# 03_SIMCOM.net
KiCad netlist of a schematic drawn in Altium Designer
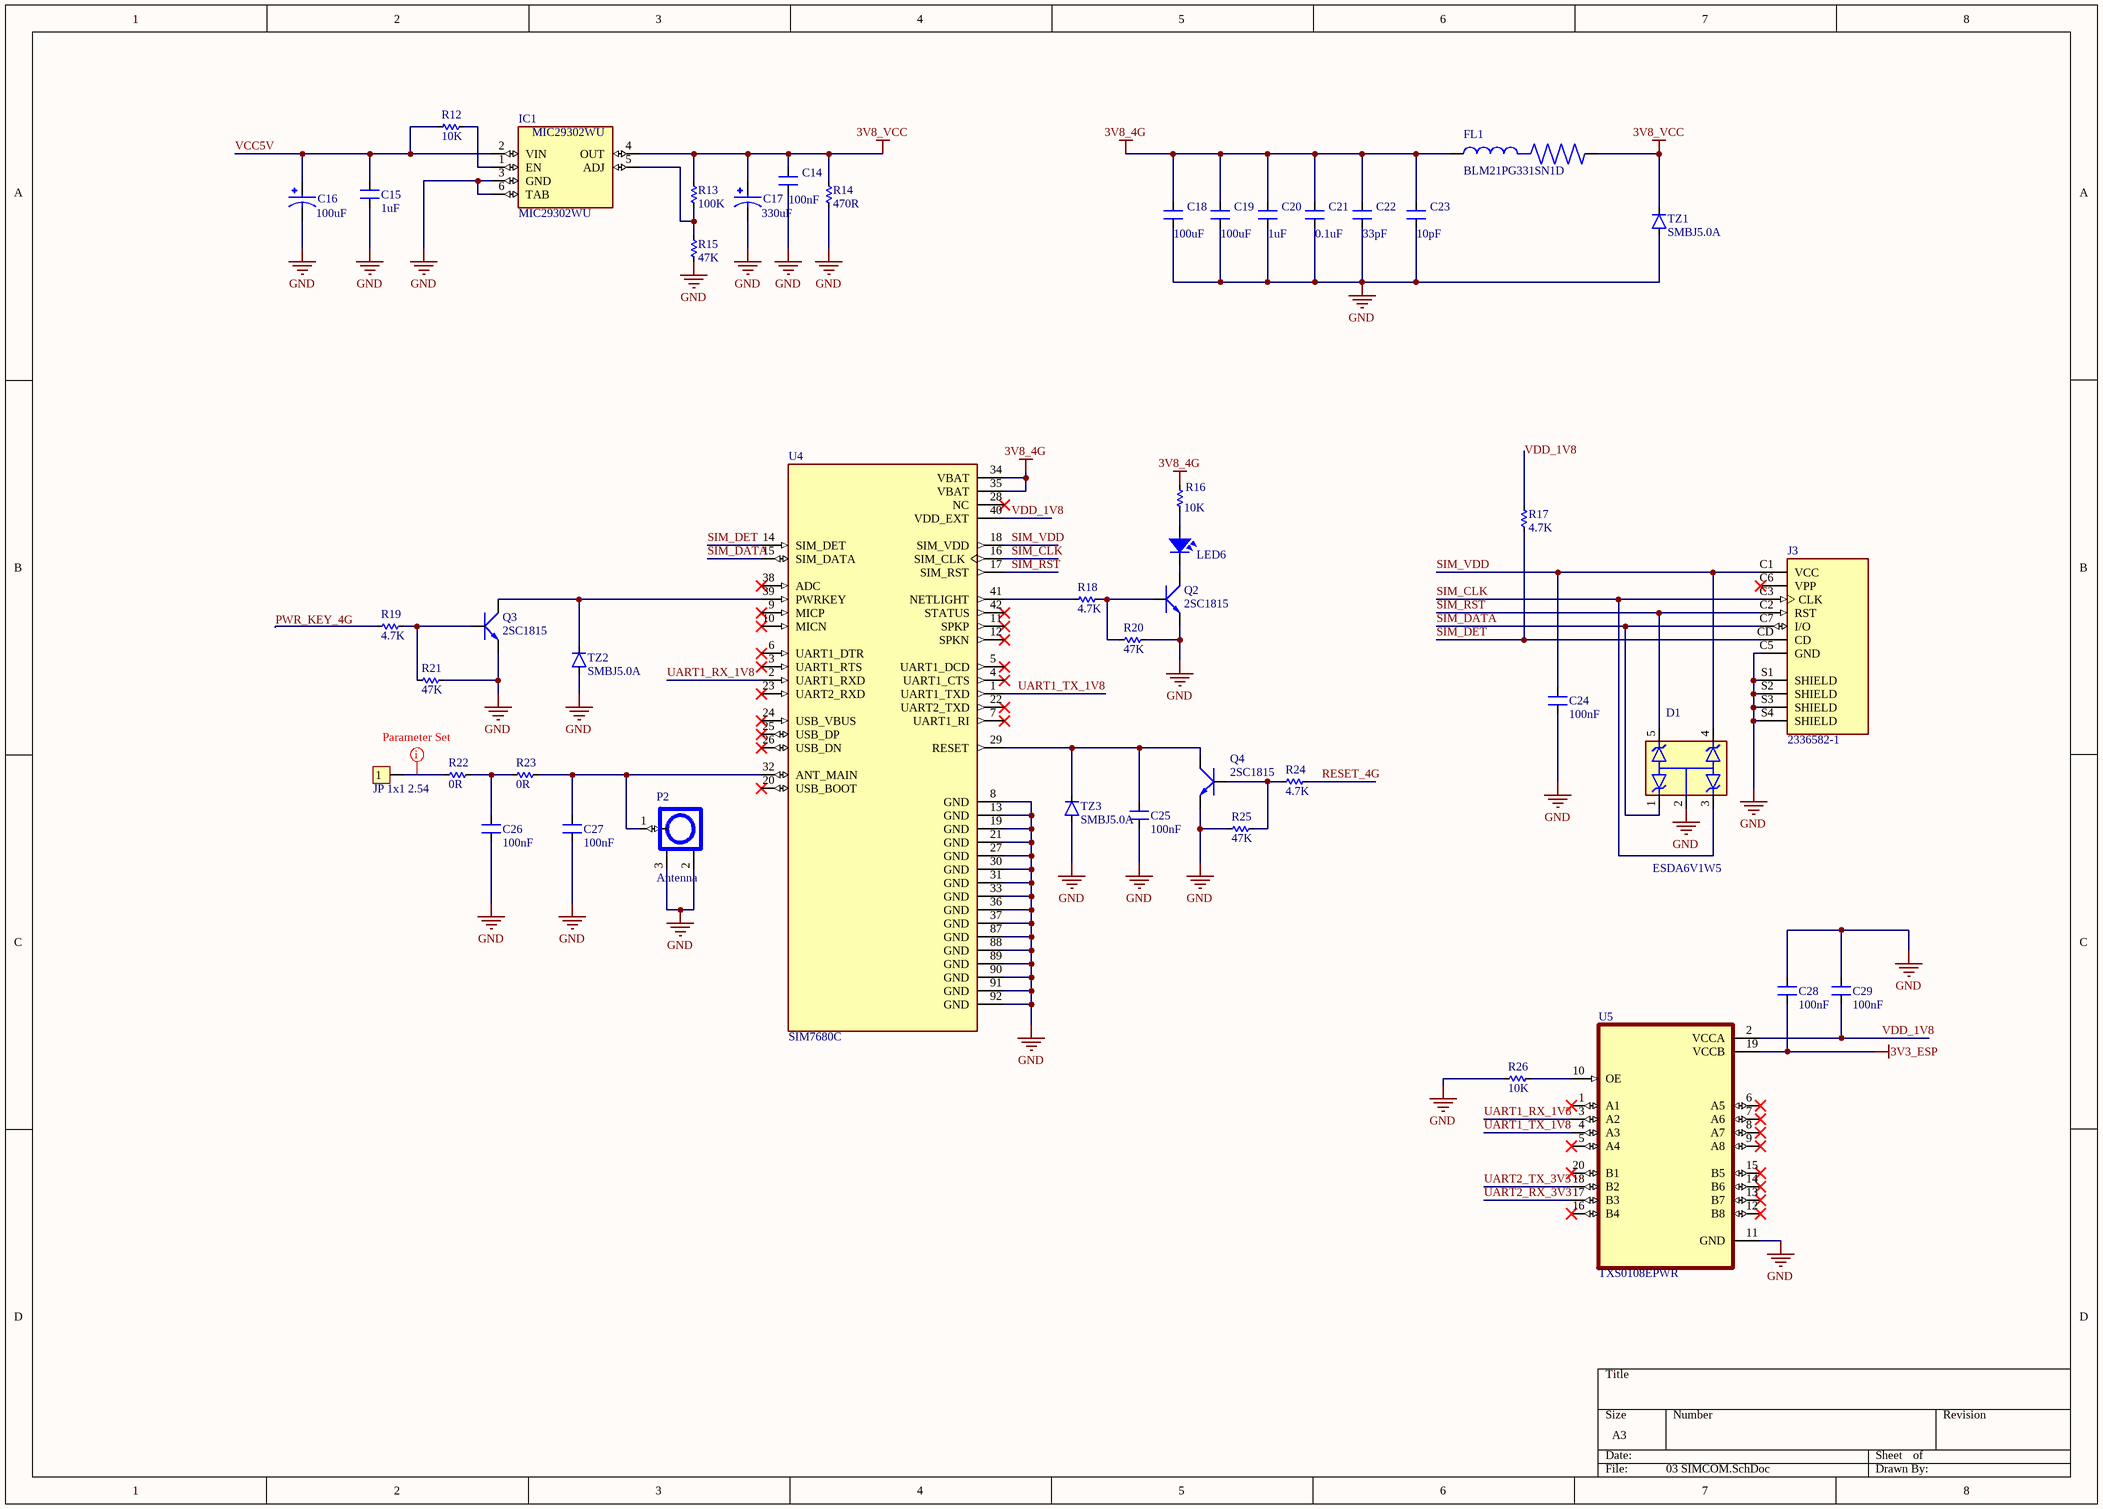
[diagram p0: 03 SIMCOM.SchDoc]

(export (version "E")
  (design (tool "Eeschema 10.0.6"))
  (components
    (comp (ref "C14")
      (value "100nF")
      (footprint "HuanHaui_FEETEAM:C 0603")
      (libsource (lib "THU_VIEN_TONG") (part "CAP_SMD"))
    )
    (comp (ref "C15")
      (value "1uF")
      (footprint "HuanHaui_FEETEAM:C 0603")
      (description "16V")
      (libsource (lib "HuanHaui_FEETEAM") (part "CAP_SMD"))
    )
    (comp (ref "C16")
      (value "100uF")
      (footprint "CAP_TANTALUM_3528")
      (description "Capacitor, Tantalum")
      (fields (field (name "MF") "AVX") (field (name "MP") "TAJB475K025RNJ"))
      (libsource (lib "My Library") (part "CAP_TANTALUM_SMD"))
    )
    (comp (ref "C17")
      (value "330uF")
      (footprint "CAP_TANTALUM_3528")
      (description "Capacitor, Tantalum")
      (fields (field (name "MF") "AVX") (field (name "MP") "TAJB475K025RNJ"))
      (libsource (lib "My Library") (part "CAP_TANTALUM_SMD"))
    )
    (comp (ref "C18")
      (value "100uF")
      (footprint "HuanHaui_FEETEAM:C 0603")
      (libsource (lib "THU_VIEN_TONG") (part "CAP_SMD"))
    )
    (comp (ref "C19")
      (value "100uF")
      (footprint "HuanHaui_FEETEAM:C 0603")
      (libsource (lib "THU_VIEN_TONG") (part "CAP_SMD"))
    )
    (comp (ref "C20")
      (value "1uF")
      (footprint "HuanHaui_FEETEAM:C 0603")
      (libsource (lib "THU_VIEN_TONG") (part "CAP_SMD"))
    )
    (comp (ref "C21")
      (value "0.1uF")
      (footprint "HuanHaui_FEETEAM:C 0603")
      (libsource (lib "THU_VIEN_TONG") (part "CAP_SMD"))
    )
    (comp (ref "C22")
      (value "33pF")
      (footprint "HuanHaui_FEETEAM:C 0603")
      (libsource (lib "THU_VIEN_TONG") (part "CAP_SMD"))
    )
    (comp (ref "C23")
      (value "10pF")
      (footprint "HuanHaui_FEETEAM:C 0603")
      (libsource (lib "THU_VIEN_TONG") (part "CAP_SMD"))
    )
    (comp (ref "C24")
      (value "100nF")
      (footprint "HuanHaui_FEETEAM:C 0603")
      (libsource (lib "HuanHaui_FEETEAM") (part "CAP_SMD"))
    )
    (comp (ref "C25")
      (value "100nF")
      (footprint "HuanHaui_FEETEAM:C 0603")
      (libsource (lib "HuanHaui_FEETEAM") (part "CAP_SMD"))
    )
    (comp (ref "C26")
      (value "100nF")
      (footprint "HuanHaui_FEETEAM:C 0603")
      (libsource (lib "HuanHaui_FEETEAM") (part "CAP_SMD"))
    )
    (comp (ref "C27")
      (value "100nF")
      (footprint "HuanHaui_FEETEAM:C 0603")
      (libsource (lib "HuanHaui_FEETEAM") (part "CAP_SMD"))
    )
    (comp (ref "C28")
      (value "100nF")
      (footprint "HuanHaui_FEETEAM:C 0603")
      (libsource (lib "HuanHaui_FEETEAM") (part "CAP_SMD"))
    )
    (comp (ref "C29")
      (value "100nF")
      (footprint "HuanHaui_FEETEAM:C 0603")
      (libsource (lib "HuanHaui_FEETEAM") (part "CAP_SMD"))
    )
    (comp (ref "D1")
      (value "ESDA6V1W5")
      (footprint "SOT65P210X110-5N")
      (description "- Clamp - Ipp Tvs Diode Surface Mount SOT-323-5")
      (fields (field (name "MF") "STMicroelectronics"))
      (libsource (lib "MinhNguyenCao") (part "ESDA6V1W5"))
    )
    (comp (ref "FL1")
      (value "BLM21PG331SN1D")
      (footprint "BEADC2012X105N")
      (description "SMD Ferrite 0805 330 Ohm +-25% 6000mA")
      (libsource (lib "MinhNguyenCao") (part "BLM21PG331SN1D"))
    )
    (comp (ref "IC1")
      (value "MIC29302WU")
      (footprint "MIC29302WU")
      (fields (field (name "MF") "{'manufacturer': u'Microchip Technology'}"))
      (libsource (lib "MinhNguyenCao") (part "MIC29302WU"))
    )
    (comp (ref "J3")
      (value "2336582-1")
      (footprint "TE_2336582-1")
      (description "PUSH-PUSH NANO SIM CONNECTOR")
      (libsource (lib "MinhNguyenCao") (part "2336582-1"))
    )
    (comp (ref "JP1")
      (value "JP 1x1 2.54")
      (footprint "JP 1x1 DT")
      (description "Cắm")
      (libsource (lib "Jump") (part "JP 1x1 2.54 Duc Cong"))
    )
    (comp (ref "LED6")
      (value "LED")
      (footprint "My Library:LED-0603")
      (libsource (lib "My Library") (part "LED SMD"))
    )
    (comp (ref "P2")
      (value "Antenna")
      (footprint "IPXS")
      (description "Antenna GSM GPS")
      (libsource (lib "My Library") (part "IPXSx66"))
    )
    (comp (ref "Q2")
      (value "2SC1815")
      (footprint "SOT23-321")
      (description "NPN 600mW, ECB")
      (libsource (lib "My Library") (part "2SC1815"))
    )
    (comp (ref "Q3")
      (value "2SC1815")
      (footprint "SOT23-321")
      (description "NPN 600mW, ECB")
      (libsource (lib "My Library") (part "2SC1815"))
    )
    (comp (ref "Q4")
      (value "2SC1815")
      (footprint "SOT23-321")
      (description "NPN 600mW, ECB")
      (libsource (lib "My Library") (part "2SC1815"))
    )
    (comp (ref "R12")
      (value "10K")
      (footprint "HuanHaui_FEETEAM:RES-SMD-0603")
      (description "RES_SMD")
      (fields
        (field (name "MANUFACTURER") "Generic Components")
        (field (name "PUBLISHER") "Altium Hobart Technology Centre")
      )
      (libsource (lib "HuanHaui_FEETEAM") (part "Res-SMD"))
    )
    (comp (ref "R13")
      (value "100K")
      (footprint "HuanHaui_FEETEAM:RES-SMD-0603")
      (description "RES_SMD")
      (fields
        (field (name "MANUFACTURER") "Generic Components")
        (field (name "PUBLISHER") "Altium Hobart Technology Centre")
      )
      (libsource (lib "HuanHaui_FEETEAM") (part "Res-SMD"))
    )
    (comp (ref "R14")
      (value "470R")
      (footprint "HuanHaui_FEETEAM:RES-SMD-0603")
      (description "RES_SMD")
      (fields
        (field (name "MANUFACTURER") "Generic Components")
        (field (name "PUBLISHER") "Altium Hobart Technology Centre")
      )
      (libsource (lib "HuanHaui_FEETEAM") (part "Res-SMD"))
    )
    (comp (ref "R15")
      (value "47K")
      (footprint "HuanHaui_FEETEAM:RES-SMD-0603")
      (description "RES_SMD")
      (fields
        (field (name "MANUFACTURER") "Generic Components")
        (field (name "PUBLISHER") "Altium Hobart Technology Centre")
      )
      (libsource (lib "HuanHaui_FEETEAM") (part "Res-SMD"))
    )
    (comp (ref "R16")
      (value "10K")
      (footprint "HuanHaui_FEETEAM:RES-SMD-0603")
      (description "RES_SMD")
      (fields
        (field (name "MANUFACTURER") "Generic Components")
        (field (name "PUBLISHER") "Altium Hobart Technology Centre")
      )
      (libsource (lib "HuanHaui_FEETEAM") (part "Res-SMD"))
    )
    (comp (ref "R17")
      (value "4.7K")
      (footprint "HuanHaui_FEETEAM:RES-SMD-0603")
      (description "RES_SMD")
      (fields
        (field (name "MANUFACTURER") "Generic Components")
        (field (name "PUBLISHER") "Altium Hobart Technology Centre")
      )
      (libsource (lib "HuanHaui_FEETEAM") (part "Res-SMD"))
    )
    (comp (ref "R18")
      (value "4.7K")
      (footprint "HuanHaui_FEETEAM:RES-SMD-0603")
      (description "RES_SMD")
      (fields
        (field (name "MANUFACTURER") "Generic Components")
        (field (name "PUBLISHER") "Altium Hobart Technology Centre")
      )
      (libsource (lib "HuanHaui_FEETEAM") (part "Res-SMD"))
    )
    (comp (ref "R19")
      (value "4.7K")
      (footprint "HuanHaui_FEETEAM:RES-SMD-0603")
      (description "RES_SMD")
      (fields
        (field (name "MANUFACTURER") "Generic Components")
        (field (name "PUBLISHER") "Altium Hobart Technology Centre")
      )
      (libsource (lib "HuanHaui_FEETEAM") (part "Res-SMD"))
    )
    (comp (ref "R20")
      (value "47K")
      (footprint "HuanHaui_FEETEAM:RES-SMD-0603")
      (description "RES_SMD")
      (fields
        (field (name "MANUFACTURER") "Generic Components")
        (field (name "PUBLISHER") "Altium Hobart Technology Centre")
      )
      (libsource (lib "HuanHaui_FEETEAM") (part "Res-SMD"))
    )
    (comp (ref "R21")
      (value "47K")
      (footprint "HuanHaui_FEETEAM:RES-SMD-0603")
      (description "RES_SMD")
      (fields
        (field (name "MANUFACTURER") "Generic Components")
        (field (name "PUBLISHER") "Altium Hobart Technology Centre")
      )
      (libsource (lib "HuanHaui_FEETEAM") (part "Res-SMD"))
    )
    (comp (ref "R22")
      (value "0R")
      (footprint "HuanHaui_FEETEAM:RES-SMD-0603")
      (description "RES_SMD")
      (fields
        (field (name "MANUFACTURER") "Generic Components")
        (field (name "PUBLISHER") "Altium Hobart Technology Centre")
      )
      (libsource (lib "HuanHaui_FEETEAM") (part "Res-SMD"))
    )
    (comp (ref "R23")
      (value "0R")
      (footprint "HuanHaui_FEETEAM:RES-SMD-0603")
      (description "RES_SMD")
      (fields
        (field (name "MANUFACTURER") "Generic Components")
        (field (name "PUBLISHER") "Altium Hobart Technology Centre")
      )
      (libsource (lib "HuanHaui_FEETEAM") (part "Res-SMD"))
    )
    (comp (ref "R24")
      (value "4.7K")
      (footprint "HuanHaui_FEETEAM:RES-SMD-0603")
      (description "RES_SMD")
      (fields
        (field (name "MANUFACTURER") "Generic Components")
        (field (name "PUBLISHER") "Altium Hobart Technology Centre")
      )
      (libsource (lib "HuanHaui_FEETEAM") (part "Res-SMD"))
    )
    (comp (ref "R25")
      (value "47K")
      (footprint "HuanHaui_FEETEAM:RES-SMD-0603")
      (description "RES_SMD")
      (fields
        (field (name "MANUFACTURER") "Generic Components")
        (field (name "PUBLISHER") "Altium Hobart Technology Centre")
      )
      (libsource (lib "HuanHaui_FEETEAM") (part "Res-SMD"))
    )
    (comp (ref "R26")
      (value "10K")
      (footprint "HuanHaui_FEETEAM:RES-SMD-0603")
      (description "RES_SMD")
      (fields
        (field (name "MANUFACTURER") "Generic Components")
        (field (name "PUBLISHER") "Altium Hobart Technology Centre")
      )
      (libsource (lib "HuanHaui_FEETEAM") (part "Res-SMD"))
    )
    (comp (ref "TZ1")
      (value "SMBJ5.0A")
      (footprint "SMB")
      (description "9.2V Clamp 65.3A Ipp Tvs Diode Surface Mount DO-214AA _SMBJ_")
      (fields (field (name "MF") "Littelfuse"))
      (libsource (lib "MinhNguyenCao") (part "SMBJ5.0A"))
    )
    (comp (ref "TZ2")
      (value "SMBJ5.0A")
      (footprint "SMB")
      (description "9.2V Clamp 65.3A Ipp Tvs Diode Surface Mount DO-214AA _SMBJ_")
      (fields (field (name "MF") "Littelfuse"))
      (libsource (lib "MinhNguyenCao") (part "SMBJ5.0A"))
    )
    (comp (ref "TZ3")
      (value "SMBJ5.0A")
      (footprint "SMB")
      (description "9.2V Clamp 65.3A Ipp Tvs Diode Surface Mount DO-214AA _SMBJ_")
      (fields (field (name "MF") "Littelfuse"))
      (libsource (lib "MinhNguyenCao") (part "SMBJ5.0A"))
    )
    (comp (ref "U4")
      (value "SIM7680C")
      (footprint "LCC110P1570X1760X250-42N")
      (description "Module: GSM/Bluetooth; GPRS; 2G; 1800MHz, 900MHz; 85.6kbps; SMD")
      (fields (field (name "MP") "SIM800C") (field (name "MF") "Simcom"))
      (libsource (lib "MinhNguyenCao") (part "SIM7680C"))
    )
    (comp (ref "U5")
      (value "TXS0108EPWR")
      (footprint "SOP65P640X120-20N")
      (description "8-bit bidirectional voltage-level shifter for open-drain and push-pull application")
      (fields (field (name "MF") "Texas Instruments"))
      (libsource (lib "MinhNguyenCao") (part "TXS0108EPWR"))
    )
  )
  (nets
    (net (code "1") (name "/PWR_KEY_4G") (class "Default")
      (node (ref "R19") (pin "1") (pinfunction "1_1") (pintype "passive"))
    )
    (net (code "2") (name "/RESET_4G") (class "Default")
      (node (ref "R24") (pin "2") (pinfunction "2_2") (pintype "passive"))
    )
    (net (code "3") (name "/SIM_CLK") (class "Default")
      (node (ref "D1") (pin "3") (pinfunction "3_3") (pintype "passive"))
      (node (ref "J3") (pin "C3") (pinfunction "CLK_C3") (pintype "input"))
      (node (ref "U4") (pin "16") (pinfunction "SIM_CLK_16") (pintype "output"))
    )
    (net (code "4") (name "/SIM_DATA") (class "Default")
      (node (ref "D1") (pin "1") (pinfunction "1_1") (pintype "passive"))
      (node (ref "J3") (pin "C7") (pinfunction "I/O_C7") (pintype "bidirectional"))
      (node (ref "U4") (pin "15") (pinfunction "SIM_DATA_15") (pintype "bidirectional"))
    )
    (net (code "5") (name "/SIM_DET") (class "Default")
      (node (ref "J3") (pin "CD") (pinfunction "CD_CD") (pintype "passive"))
      (node (ref "R17") (pin "2") (pinfunction "2_2") (pintype "passive"))
      (node (ref "U4") (pin "14") (pinfunction "SIM_DET_14") (pintype "input"))
    )
    (net (code "6") (name "/SIM_RST") (class "Default")
      (node (ref "D1") (pin "5") (pinfunction "5_5") (pintype "passive"))
      (node (ref "J3") (pin "C2") (pinfunction "RST_C2") (pintype "input"))
      (node (ref "U4") (pin "17") (pinfunction "SIM_RST_17") (pintype "output"))
    )
    (net (code "7") (name "/SIM_VDD") (class "Default")
      (node (ref "C24") (pin "2") (pinfunction "2_2") (pintype "passive"))
      (node (ref "D1") (pin "4") (pinfunction "4_4") (pintype "passive"))
      (node (ref "J3") (pin "C1") (pinfunction "VCC_C1") (pintype "power_in"))
      (node (ref "U4") (pin "18") (pinfunction "SIM_VDD_18") (pintype "output"))
    )
    (net (code "8") (name "/UART1_RX_1V8") (class "Default")
      (node (ref "U4") (pin "2") (pinfunction "UART1_RXD_2") (pintype "input"))
      (node (ref "U5") (pin "3") (pinfunction "A2_3") (pintype "bidirectional"))
    )
    (net (code "9") (name "/UART1_TX_1V8") (class "Default")
      (node (ref "U4") (pin "1") (pinfunction "UART1_TXD_1") (pintype "output"))
      (node (ref "U5") (pin "4") (pinfunction "A3_4") (pintype "bidirectional"))
    )
    (net (code "10") (name "/UART2_RX_3V3") (class "Default")
      (node (ref "U5") (pin "17") (pinfunction "B3_17") (pintype "bidirectional"))
    )
    (net (code "11") (name "/UART2_TX_3V3") (class "Default")
      (node (ref "U5") (pin "18") (pinfunction "B2_18") (pintype "bidirectional"))
    )
    (net (code "12") (name "/VCC5V") (class "Default")
      (node (ref "C15") (pin "2") (pinfunction "2_2") (pintype "passive"))
      (node (ref "C16") (pin "1") (pinfunction "1_1") (pintype "passive"))
      (node (ref "IC1") (pin "2") (pinfunction "VIN_2") (pintype "bidirectional"))
      (node (ref "R12") (pin "1") (pinfunction "1_1") (pintype "passive"))
    )
    (net (code "13") (name "/VDD_1V8") (class "Default")
      (node (ref "C29") (pin "1") (pinfunction "1_1") (pintype "passive"))
      (node (ref "R17") (pin "1") (pinfunction "1_1") (pintype "passive"))
      (node (ref "U4") (pin "40") (pinfunction "VDD_EXT_40") (pintype "power_in"))
      (node (ref "U5") (pin "2") (pinfunction "VCCA_2") (pintype "power_in"))
    )
    (net (code "14") (name "3V3_ESP") (class "Default")
      (node (ref "C28") (pin "1") (pinfunction "1_1") (pintype "passive"))
      (node (ref "U5") (pin "19") (pinfunction "VCCB_19") (pintype "power_in"))
    )
    (net (code "15") (name "3V8_4G") (class "Default")
      (node (ref "C18") (pin "1") (pinfunction "1_1") (pintype "passive"))
      (node (ref "C19") (pin "1") (pinfunction "1_1") (pintype "passive"))
      (node (ref "C20") (pin "1") (pinfunction "1_1") (pintype "passive"))
      (node (ref "C21") (pin "1") (pinfunction "1_1") (pintype "passive"))
      (node (ref "C22") (pin "1") (pinfunction "1_1") (pintype "passive"))
      (node (ref "C23") (pin "1") (pinfunction "1_1") (pintype "passive"))
      (node (ref "FL1") (pin "1") (pinfunction "1_1") (pintype "passive"))
      (node (ref "R16") (pin "2") (pinfunction "2_2") (pintype "passive"))
      (node (ref "U4") (pin "34") (pinfunction "VBAT_34") (pintype "power_in"))
      (node (ref "U4") (pin "35") (pinfunction "VBAT_35") (pintype "power_in"))
    )
    (net (code "16") (name "3V8_VCC") (class "Default")
      (node (ref "C14") (pin "1") (pinfunction "1_1") (pintype "passive"))
      (node (ref "C17") (pin "1") (pinfunction "1_1") (pintype "passive"))
      (node (ref "FL1") (pin "2") (pinfunction "2_2") (pintype "passive"))
      (node (ref "IC1") (pin "4") (pinfunction "OUT_4") (pintype "bidirectional"))
      (node (ref "R13") (pin "1") (pinfunction "1_1") (pintype "passive"))
      (node (ref "R14") (pin "1") (pinfunction "1_1") (pintype "passive"))
      (node (ref "TZ1") (pin "2") (pinfunction "2_2") (pintype "passive"))
    )
    (net (code "17") (name "GND") (class "Default")
      (node (ref "C14") (pin "2") (pinfunction "2_2") (pintype "passive"))
      (node (ref "C15") (pin "1") (pinfunction "1_1") (pintype "passive"))
      (node (ref "C16") (pin "2") (pinfunction "2_2") (pintype "passive"))
      (node (ref "C17") (pin "2") (pinfunction "2_2") (pintype "passive"))
      (node (ref "C18") (pin "2") (pinfunction "2_2") (pintype "passive"))
      (node (ref "C19") (pin "2") (pinfunction "2_2") (pintype "passive"))
      (node (ref "C20") (pin "2") (pinfunction "2_2") (pintype "passive"))
      (node (ref "C21") (pin "2") (pinfunction "2_2") (pintype "passive"))
      (node (ref "C22") (pin "2") (pinfunction "2_2") (pintype "passive"))
      (node (ref "C23") (pin "2") (pinfunction "2_2") (pintype "passive"))
      (node (ref "C24") (pin "1") (pinfunction "1_1") (pintype "passive"))
      (node (ref "C25") (pin "1") (pinfunction "1_1") (pintype "passive"))
      (node (ref "C26") (pin "1") (pinfunction "1_1") (pintype "passive"))
      (node (ref "C27") (pin "1") (pinfunction "1_1") (pintype "passive"))
      (node (ref "C28") (pin "2") (pinfunction "2_2") (pintype "passive"))
      (node (ref "C29") (pin "2") (pinfunction "2_2") (pintype "passive"))
      (node (ref "D1") (pin "2") (pinfunction "2_2") (pintype "passive"))
      (node (ref "IC1") (pin "3") (pinfunction "GND_3") (pintype "bidirectional"))
      (node (ref "IC1") (pin "6") (pinfunction "TAB_6") (pintype "bidirectional"))
      (node (ref "J3") (pin "C5") (pinfunction "GND_C5") (pintype "power_in"))
      (node (ref "J3") (pin "S1") (pinfunction "SHIELD_S1") (pintype "passive"))
      (node (ref "J3") (pin "S2") (pinfunction "SHIELD_S2") (pintype "passive"))
      (node (ref "J3") (pin "S3") (pinfunction "SHIELD_S3") (pintype "passive"))
      (node (ref "J3") (pin "S4") (pinfunction "SHIELD_S4") (pintype "passive"))
      (node (ref "P2") (pin "2") (pintype "passive"))
      (node (ref "P2") (pin "3") (pintype "passive"))
      (node (ref "Q2") (pin "1") (pinfunction "E_1") (pintype "passive"))
      (node (ref "Q3") (pin "1") (pinfunction "E_1") (pintype "passive"))
      (node (ref "Q4") (pin "1") (pinfunction "E_1") (pintype "passive"))
      (node (ref "R14") (pin "2") (pinfunction "2_2") (pintype "passive"))
      (node (ref "R15") (pin "2") (pinfunction "2_2") (pintype "passive"))
      (node (ref "R20") (pin "2") (pinfunction "2_2") (pintype "passive"))
      (node (ref "R21") (pin "1") (pinfunction "1_1") (pintype "passive"))
      (node (ref "R25") (pin "2") (pinfunction "2_2") (pintype "passive"))
      (node (ref "R26") (pin "2") (pinfunction "2_2") (pintype "passive"))
      (node (ref "TZ1") (pin "1") (pinfunction "1_1") (pintype "passive"))
      (node (ref "TZ2") (pin "1") (pinfunction "1_1") (pintype "passive"))
      (node (ref "TZ3") (pin "1") (pinfunction "1_1") (pintype "passive"))
      (node (ref "U4") (pin "13") (pinfunction "GND_13") (pintype "power_in"))
      (node (ref "U4") (pin "19") (pinfunction "GND_19") (pintype "power_in"))
      (node (ref "U4") (pin "21") (pinfunction "GND_21") (pintype "power_in"))
      (node (ref "U4") (pin "27") (pinfunction "GND_27") (pintype "power_in"))
      (node (ref "U4") (pin "30") (pinfunction "GND_30") (pintype "power_in"))
      (node (ref "U4") (pin "31") (pinfunction "GND_31") (pintype "power_in"))
      (node (ref "U4") (pin "33") (pinfunction "GND_33") (pintype "power_in"))
      (node (ref "U4") (pin "36") (pinfunction "GND_36") (pintype "power_in"))
      (node (ref "U4") (pin "37") (pinfunction "GND_37") (pintype "power_in"))
      (node (ref "U4") (pin "8") (pinfunction "GND_8") (pintype "power_in"))
      (node (ref "U4") (pin "87") (pinfunction "GND_87") (pintype "power_in"))
      (node (ref "U4") (pin "88") (pinfunction "GND_88") (pintype "power_in"))
      (node (ref "U4") (pin "89") (pinfunction "GND_89") (pintype "power_in"))
      (node (ref "U4") (pin "90") (pinfunction "GND_90") (pintype "power_in"))
      (node (ref "U4") (pin "91") (pinfunction "GND_91") (pintype "power_in"))
      (node (ref "U4") (pin "92") (pinfunction "GND_92") (pintype "power_in"))
      (node (ref "U5") (pin "11") (pinfunction "GND_11") (pintype "power_in"))
    )
    (net (code "18") (name "Net-(C26-Pad2)") (class "Default")
      (node (ref "C26") (pin "2") (pinfunction "2_2") (pintype "passive"))
      (node (ref "R22") (pin "1") (pinfunction "1_1") (pintype "passive"))
      (node (ref "R23") (pin "2") (pinfunction "2_2") (pintype "passive"))
    )
    (net (code "19") (name "Net-(IC1-ADJ)") (class "Default")
      (node (ref "IC1") (pin "5") (pinfunction "ADJ_5") (pintype "bidirectional"))
      (node (ref "R13") (pin "2") (pinfunction "2_2") (pintype "passive"))
      (node (ref "R15") (pin "1") (pinfunction "1_1") (pintype "passive"))
    )
    (net (code "20") (name "Net-(IC1-EN)") (class "Default")
      (node (ref "IC1") (pin "1") (pinfunction "EN_1") (pintype "bidirectional"))
      (node (ref "R12") (pin "2") (pinfunction "2_2") (pintype "passive"))
    )
    (net (code "21") (name "Net-(JP1-Pad1)") (class "Default")
      (node (ref "JP1") (pin "1") (pinfunction "1_1") (pintype "passive"))
      (node (ref "R22") (pin "2") (pinfunction "2_2") (pintype "passive"))
    )
    (net (code "22") (name "Net-(LED6-Pad1)") (class "Default")
      (node (ref "LED6") (pin "1") (pinfunction "1_1") (pintype "passive"))
      (node (ref "R16") (pin "1") (pinfunction "1_1") (pintype "passive"))
    )
    (net (code "23") (name "Net-(Q2-B)") (class "Default")
      (node (ref "Q2") (pin "3") (pinfunction "B_3") (pintype "passive"))
      (node (ref "R18") (pin "2") (pinfunction "2_2") (pintype "passive"))
      (node (ref "R20") (pin "1") (pinfunction "1_1") (pintype "passive"))
    )
    (net (code "24") (name "Net-(Q2-C)") (class "Default")
      (node (ref "LED6") (pin "2") (pinfunction "2_2") (pintype "passive"))
      (node (ref "Q2") (pin "2") (pinfunction "C_2") (pintype "passive"))
    )
    (net (code "25") (name "Net-(Q3-B)") (class "Default")
      (node (ref "Q3") (pin "3") (pinfunction "B_3") (pintype "passive"))
      (node (ref "R19") (pin "2") (pinfunction "2_2") (pintype "passive"))
      (node (ref "R21") (pin "2") (pinfunction "2_2") (pintype "passive"))
    )
    (net (code "26") (name "Net-(Q3-C)") (class "Default")
      (node (ref "Q3") (pin "2") (pinfunction "C_2") (pintype "passive"))
      (node (ref "TZ2") (pin "2") (pinfunction "2_2") (pintype "passive"))
      (node (ref "U4") (pin "39") (pinfunction "PWRKEY_39") (pintype "input"))
    )
    (net (code "27") (name "Net-(Q4-B)") (class "Default")
      (node (ref "Q4") (pin "3") (pinfunction "B_3") (pintype "passive"))
      (node (ref "R24") (pin "1") (pinfunction "1_1") (pintype "passive"))
      (node (ref "R25") (pin "1") (pinfunction "1_1") (pintype "passive"))
    )
    (net (code "28") (name "Net-(Q4-C)") (class "Default")
      (node (ref "C25") (pin "2") (pinfunction "2_2") (pintype "passive"))
      (node (ref "Q4") (pin "2") (pinfunction "C_2") (pintype "passive"))
      (node (ref "TZ3") (pin "2") (pinfunction "2_2") (pintype "passive"))
      (node (ref "U4") (pin "29") (pinfunction "RESET_29") (pintype "output"))
    )
    (net (code "29") (name "Net-(U4-ANT_MAIN)") (class "Default")
      (node (ref "C27") (pin "2") (pinfunction "2_2") (pintype "passive"))
      (node (ref "P2") (pin "1") (pintype "bidirectional"))
      (node (ref "R23") (pin "1") (pinfunction "1_1") (pintype "passive"))
      (node (ref "U4") (pin "32") (pinfunction "ANT_MAIN_32") (pintype "bidirectional"))
    )
    (net (code "30") (name "Net-(U4-NETLIGHT)") (class "Default")
      (node (ref "R18") (pin "1") (pinfunction "1_1") (pintype "passive"))
      (node (ref "U4") (pin "41") (pinfunction "NETLIGHT_41") (pintype "output"))
    )
    (net (code "31") (name "Net-(U5-OE)") (class "Default")
      (node (ref "R26") (pin "1") (pinfunction "1_1") (pintype "passive"))
      (node (ref "U5") (pin "10") (pinfunction "OE_10") (pintype "input"))
    )
    (net (code "32") (name "unconnected-(J3-VPP-PadC6)") (class "Default")
      (node (ref "J3") (pin "C6") (pinfunction "VPP_C6") (pintype "power_in+no_connect"))
    )
    (net (code "33") (name "unconnected-(U4-ADC-Pad38)") (class "Default")
      (node (ref "U4") (pin "38") (pinfunction "ADC_38") (pintype "input+no_connect"))
    )
    (net (code "34") (name "unconnected-(U4-MICN-Pad10)") (class "Default")
      (node (ref "U4") (pin "10") (pinfunction "MICN_10") (pintype "input+no_connect"))
    )
    (net (code "35") (name "unconnected-(U4-MICP-Pad9)") (class "Default")
      (node (ref "U4") (pin "9") (pinfunction "MICP_9") (pintype "input+no_connect"))
    )
    (net (code "36") (name "unconnected-(U4-NC-Pad28)") (class "Default")
      (node (ref "U4") (pin "28") (pinfunction "NC_28") (pintype "power_in+no_connect"))
    )
    (net (code "37") (name "unconnected-(U4-SPKN-Pad12)") (class "Default")
      (node (ref "U4") (pin "12") (pinfunction "SPKN_12") (pintype "output+no_connect"))
    )
    (net (code "38") (name "unconnected-(U4-SPKP-Pad11)") (class "Default")
      (node (ref "U4") (pin "11") (pinfunction "SPKP_11") (pintype "output+no_connect"))
    )
    (net (code "39") (name "unconnected-(U4-STATUS-Pad42)") (class "Default")
      (node (ref "U4") (pin "42") (pinfunction "STATUS_42") (pintype "output+no_connect"))
    )
    (net (code "40") (name "unconnected-(U4-UART1_CTS-Pad4)") (class "Default")
      (node (ref "U4") (pin "4") (pinfunction "UART1_CTS_4") (pintype "output+no_connect"))
    )
    (net (code "41") (name "unconnected-(U4-UART1_DCD-Pad5)") (class "Default")
      (node (ref "U4") (pin "5") (pinfunction "UART1_DCD_5") (pintype "output+no_connect"))
    )
    (net (code "42") (name "unconnected-(U4-UART1_DTR-Pad6)") (class "Default")
      (node (ref "U4") (pin "6") (pinfunction "UART1_DTR_6") (pintype "input+no_connect"))
    )
    (net (code "43") (name "unconnected-(U4-UART1_RI-Pad7)") (class "Default")
      (node (ref "U4") (pin "7") (pinfunction "UART1_RI_7") (pintype "output+no_connect"))
    )
    (net (code "44") (name "unconnected-(U4-UART1_RTS-Pad3)") (class "Default")
      (node (ref "U4") (pin "3") (pinfunction "UART1_RTS_3") (pintype "input+no_connect"))
    )
    (net (code "45") (name "unconnected-(U4-UART2_RXD-Pad23)") (class "Default")
      (node (ref "U4") (pin "23") (pinfunction "UART2_RXD_23") (pintype "input+no_connect"))
    )
    (net (code "46") (name "unconnected-(U4-UART2_TXD-Pad22)") (class "Default")
      (node (ref "U4") (pin "22") (pinfunction "UART2_TXD_22") (pintype "output+no_connect"))
    )
    (net (code "47") (name "unconnected-(U4-USB_BOOT-Pad20)") (class "Default")
      (node (ref "U4") (pin "20") (pinfunction "USB_BOOT_20") (pintype "bidirectional+no_connect"))
    )
    (net (code "48") (name "unconnected-(U4-USB_DN-Pad26)") (class "Default")
      (node (ref "U4") (pin "26") (pinfunction "USB_DN_26") (pintype "bidirectional+no_connect"))
    )
    (net (code "49") (name "unconnected-(U4-USB_DP-Pad25)") (class "Default")
      (node (ref "U4") (pin "25") (pinfunction "USB_DP_25") (pintype "bidirectional+no_connect"))
    )
    (net (code "50") (name "unconnected-(U4-USB_VBUS-Pad24)") (class "Default")
      (node (ref "U4") (pin "24") (pinfunction "USB_VBUS_24") (pintype "input+no_connect"))
    )
    (net (code "51") (name "unconnected-(U5-A1-Pad1)") (class "Default")
      (node (ref "U5") (pin "1") (pinfunction "A1_1") (pintype "bidirectional+no_connect"))
    )
    (net (code "52") (name "unconnected-(U5-A4-Pad5)") (class "Default")
      (node (ref "U5") (pin "5") (pinfunction "A4_5") (pintype "bidirectional+no_connect"))
    )
    (net (code "53") (name "unconnected-(U5-A5-Pad6)") (class "Default")
      (node (ref "U5") (pin "6") (pinfunction "A5_6") (pintype "bidirectional+no_connect"))
    )
    (net (code "54") (name "unconnected-(U5-A6-Pad7)") (class "Default")
      (node (ref "U5") (pin "7") (pinfunction "A6_7") (pintype "bidirectional+no_connect"))
    )
    (net (code "55") (name "unconnected-(U5-A7-Pad8)") (class "Default")
      (node (ref "U5") (pin "8") (pinfunction "A7_8") (pintype "bidirectional+no_connect"))
    )
    (net (code "56") (name "unconnected-(U5-A8-Pad9)") (class "Default")
      (node (ref "U5") (pin "9") (pinfunction "A8_9") (pintype "bidirectional+no_connect"))
    )
    (net (code "57") (name "unconnected-(U5-B1-Pad20)") (class "Default")
      (node (ref "U5") (pin "20") (pinfunction "B1_20") (pintype "bidirectional+no_connect"))
    )
    (net (code "58") (name "unconnected-(U5-B4-Pad16)") (class "Default")
      (node (ref "U5") (pin "16") (pinfunction "B4_16") (pintype "bidirectional+no_connect"))
    )
    (net (code "59") (name "unconnected-(U5-B5-Pad15)") (class "Default")
      (node (ref "U5") (pin "15") (pinfunction "B5_15") (pintype "bidirectional+no_connect"))
    )
    (net (code "60") (name "unconnected-(U5-B6-Pad14)") (class "Default")
      (node (ref "U5") (pin "14") (pinfunction "B6_14") (pintype "bidirectional+no_connect"))
    )
    (net (code "61") (name "unconnected-(U5-B7-Pad13)") (class "Default")
      (node (ref "U5") (pin "13") (pinfunction "B7_13") (pintype "bidirectional+no_connect"))
    )
    (net (code "62") (name "unconnected-(U5-B8-Pad12)") (class "Default")
      (node (ref "U5") (pin "12") (pinfunction "B8_12") (pintype "bidirectional+no_connect"))
    )
  )
)
